# FRONT-UNIT-7.net
KiCad netlist of a schematic drawn in Altium Designer
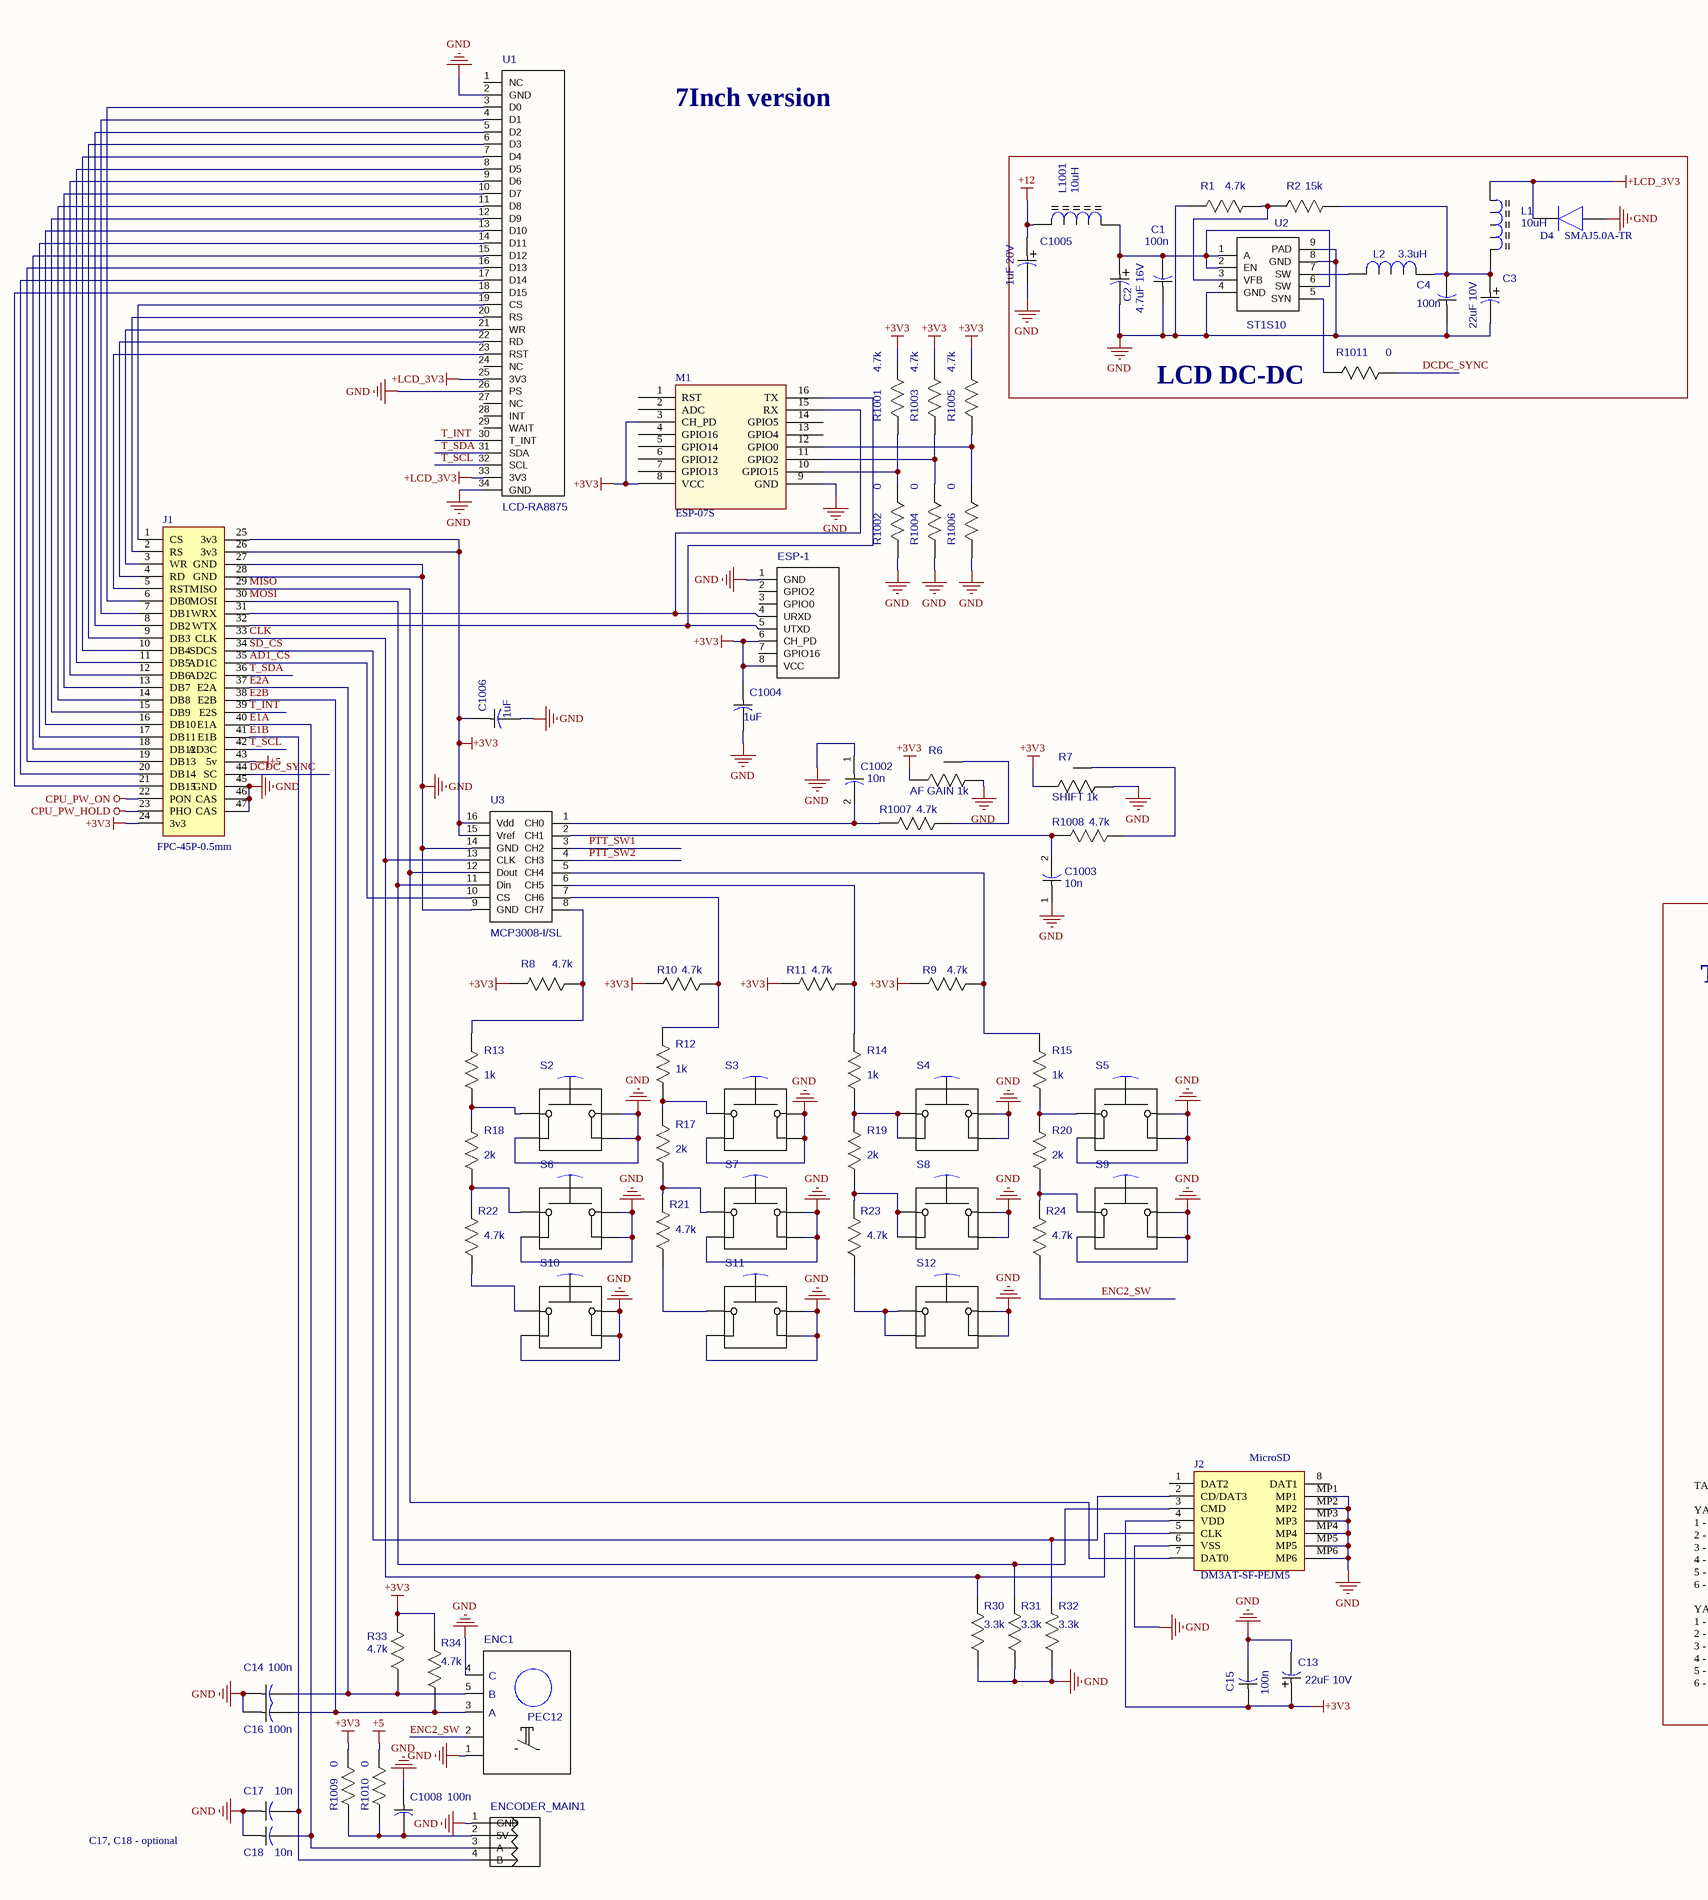
[diagram p0: FRONT-UNIT-7.SCHDOC, left]
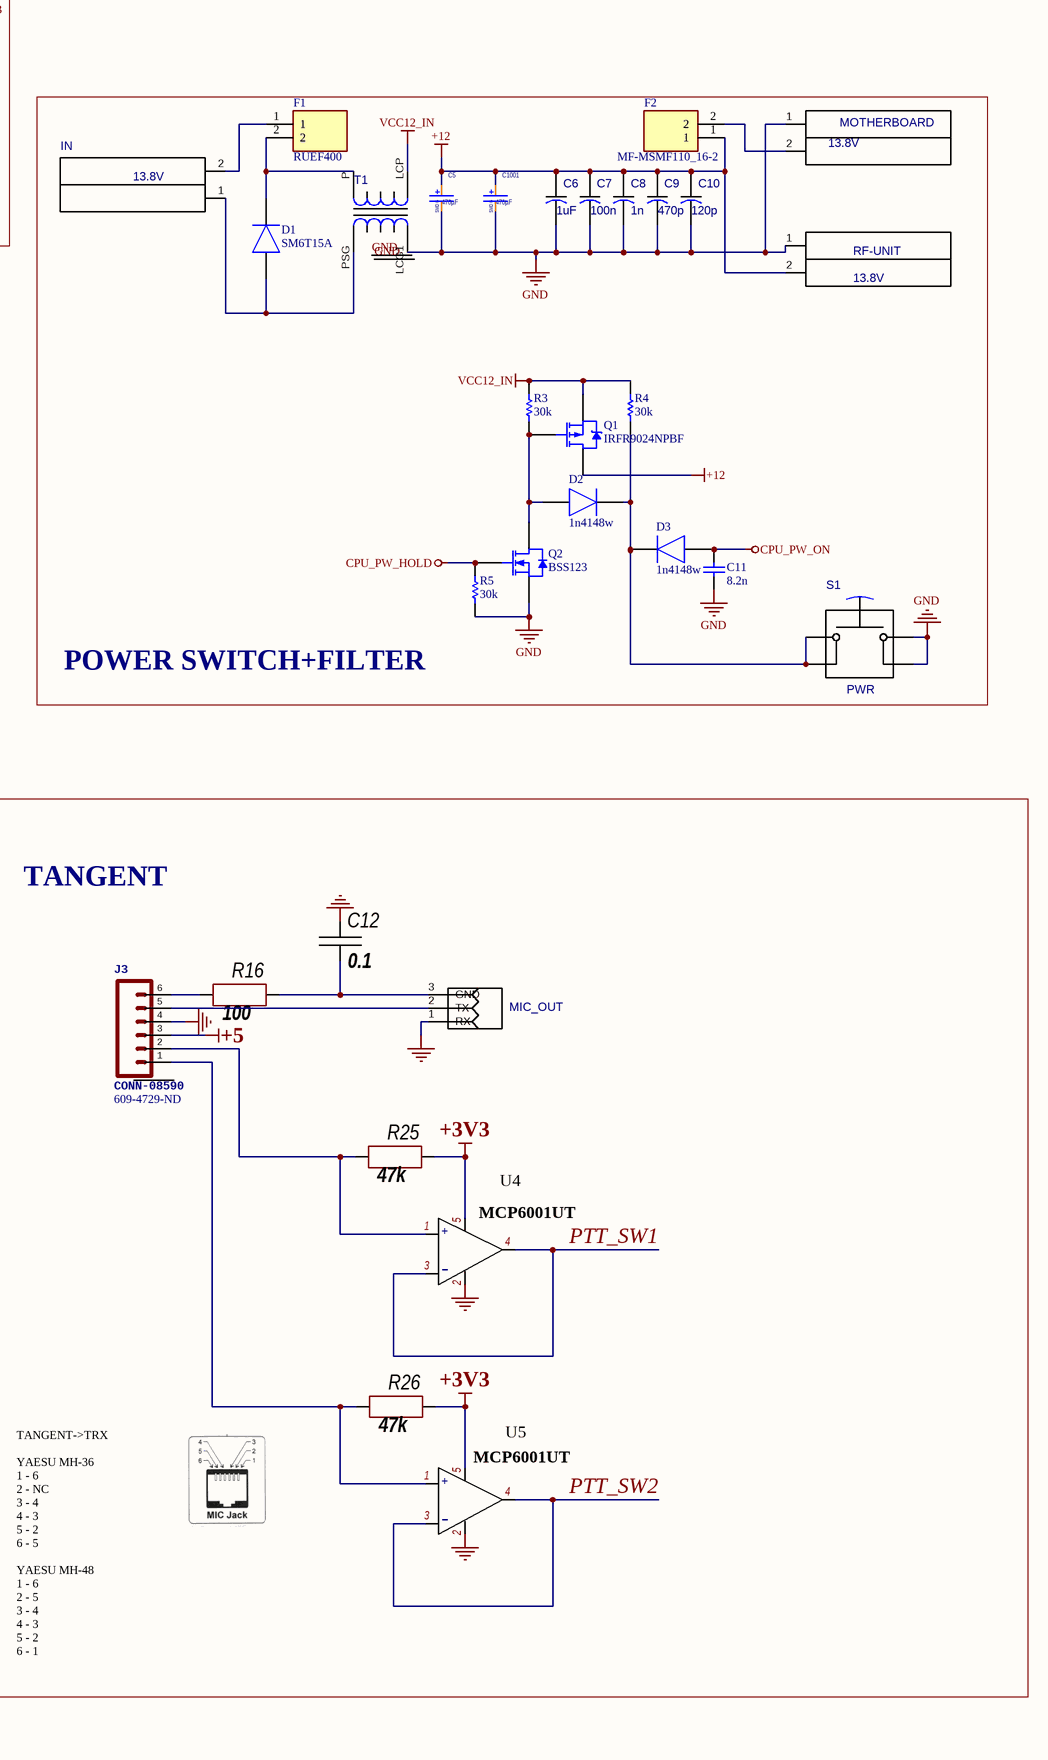
[diagram p1: FRONT-UNIT-7.SCHDOC, right]

(export (version "E")
  (design (tool "Eeschema 10.0.6"))
  (components
    (comp (ref "C1")
      (value "100n")
      (footprint "CAP_0805")
      (description "CAP_0805")
      (libsource (lib "*") (part "CAP_0805"))
    )
    (comp (ref "C2")
      (value "4.7uF 16V")
      (footprint "SMC")
      (description "CAPAE_6.6x6.6h5.4")
      (libsource (lib "*") (part "CAPAE_6.6x6.6h5.4"))
    )
    (comp (ref "C3")
      (value "22uF 10V")
      (footprint "CAPAE_4.3x4.3h5.4")
      (description "CAPAE_4.3x4.3h5.4")
      (libsource (lib "*") (part "CAPAE_4.3x4.3h5.4"))
    )
    (comp (ref "C4")
      (value "100n")
      (footprint "CAP_0805")
      (description "CAP_0805")
      (libsource (lib "FRONT-UNIT-7INCH") (part "CAP_0805"))
    )
    (comp (ref "C5")
      (value "470µF")
      (footprint "SMD-G-10X10.2")
      (description "CAP ALUM 470UF 20% 25V SMD")
      (fields
        (field (name "TOLERANCE") "±20 %")
        (field (name "VOLTAGE") "25V")
        (field (name "PUBLISHER") "Catcatcat Electronics")
      )
      (libsource (lib "CapacitorElectrolytic") (part "SMD-G 470uF 25V"))
    )
    (comp (ref "C6")
      (value "1uF")
      (footprint "CAP_1206")
      (description "CAP_1206")
      (libsource (lib "*") (part "CAP_1206"))
    )
    (comp (ref "C7")
      (value "100n")
      (footprint "CAP_1206")
      (description "CAP_1206")
      (libsource (lib "*") (part "CAP_1206"))
    )
    (comp (ref "C8")
      (value "1n")
      (footprint "CAP_1206")
      (description "CAP_1206")
      (libsource (lib "*") (part "CAP_1206"))
    )
    (comp (ref "C9")
      (value "470p")
      (footprint "CAP_1206")
      (description "CAP_1206")
      (libsource (lib "*") (part "CAP_1206"))
    )
    (comp (ref "C10")
      (value "120p")
      (footprint "CAP_1206")
      (description "CAP_1206")
      (libsource (lib "FRONT-UNIT-7INCH") (part "CAP_1206"))
    )
    (comp (ref "C11")
      (value "8.2n")
      (footprint "CAPC2013X94X50LL20T25")
      (description "CAP_1206")
      (fields
        (field (name "MANUFACTURER") "AVX Interconnect / Elco")
        (field (name "PART NUMBER") "08055C822KAT2A")
      )
      (libsource (lib "Altium Content Vault") (part "CAP"))
    )
    (comp (ref "C12")
      (value "0.1")
      (footprint "CH0805C")
      (libsource (lib "FRONT-UNIT-7INCH") (part "Capacitor"))
    )
    (comp (ref "C13")
      (value "22uF 10V")
      (footprint "EEEFC_sizeB")
      (description "EEEFC_sizeB")
      (libsource (lib "*") (part "EEEFC_sizeB"))
    )
    (comp (ref "C14")
      (value "100n")
      (footprint "CAP_0805")
      (description "CAP_0805")
      (libsource (lib "*") (part "CAP_0805"))
    )
    (comp (ref "C15")
      (value "100n")
      (footprint "CAP_0805")
      (description "CAP_0805")
      (libsource (lib "*") (part "CAP_0805"))
    )
    (comp (ref "C16")
      (value "100n")
      (footprint "CAP_0805")
      (description "CAP_0805")
      (libsource (lib "*") (part "CAP_0805"))
    )
    (comp (ref "C17")
      (value "10n")
      (footprint "CAP_0805")
      (description "CAP_0805")
      (libsource (lib "*") (part "CAP_0805"))
    )
    (comp (ref "C18")
      (value "10n")
      (footprint "CAP_0805")
      (description "CAP_0805")
      (libsource (lib "*") (part "CAP_0805"))
    )
    (comp (ref "C1001")
      (value "470µF")
      (footprint "SMD-G-10X10.2")
      (description "CAP ALUM 470UF 20% 25V SMD")
      (fields
        (field (name "TOLERANCE") "±20 %")
        (field (name "VOLTAGE") "25V")
        (field (name "PUBLISHER") "Catcatcat Electronics")
      )
      (libsource (lib "CapacitorElectrolytic") (part "SMD-G 470uF 25V"))
    )
    (comp (ref "C1002")
      (value "10n")
      (footprint "CAP_0805")
      (libsource (lib "FRONT-UNIT-7") (part "CAP_0805"))
    )
    (comp (ref "C1003")
      (value "10n")
      (footprint "CAP_0805")
      (libsource (lib "FRONT-UNIT-7") (part "CAP_0805"))
    )
    (comp (ref "C1004")
      (value "1uF")
      (footprint "CAP_1206")
      (description "CAP_1206")
      (libsource (lib "*") (part "CAP_1206"))
    )
    (comp (ref "C1005")
      (value "1uF 20V")
      (footprint "CAPAE_4.3x4.3h5.4")
      (description "CAPAE_4.3x4.3h5.4")
      (libsource (lib "*") (part "CAPAE_4.3x4.3h5.4"))
    )
    (comp (ref "C1006")
      (value "1uF")
      (footprint "CAP_1206")
      (description "CAP_1206")
      (libsource (lib "*") (part "CAP_1206"))
    )
    (comp (ref "C1008")
      (value "100n")
      (footprint "CAP_0805")
      (description "CAP_0805")
      (libsource (lib "*") (part "CAP_0805"))
    )
    (comp (ref "D1")
      (value "SM6T15A")
      (footprint "SamacSys:SMBJ36CATR")
      (description "Diode")
      (fields (field (name "MOUSER PART NUMBER") "511-SM6T15A") (field (name "RS PART NUMBER") "4864915P"))
      (libsource (lib "*") (part "SM6T15A"))
    )
    (comp (ref "D2")
      (value "1n4148w")
      (footprint "SamacSys:SOD3716X135N")
      (description "Diode")
      (libsource (lib "*") (part "1n4148w"))
    )
    (comp (ref "D3")
      (value "1n4148w")
      (footprint "SamacSys:SOD3716X135N")
      (description "Diode")
      (libsource (lib "*") (part "1n4148w"))
    )
    (comp (ref "D4")
      (value "SMAJ5.0A-TR")
      (footprint "SamacSys:SMBJ36CATR")
      (description "Diode")
      (fields
        (field (name "MANUFACTURER_PART_NUMBER") "SMLVT3V3")
        (field (name "MOUSER PART NUMBER") "511-SMLVT3V3")
      )
      (libsource (lib "*") (part "SMLVT3V3"))
    )
    (comp (ref "ENC1") (value "PEC12") (footprint "PEC12") (libsource (lib "*") (part "PEC12")))
    (comp (ref "ENCODER_MAIN1")
      (value "OPTICAL ENCODER")
      (footprint "644456-4")
      (libsource (lib "*") (part "644456-4"))
    )
    (comp (ref "ESP-1")
      (value "ESP-01 ESP8266")
      (footprint "ESP-01 ESP8266")
      (libsource (lib "*") (part "ESP-01 ESP8266"))
    )
    (comp (ref "F1")
      (value "RUEF400")
      (footprint "SamacSys:RUEF400")
      (description "Fuse")
      (fields (field (name "MOUSER PART NUMBER") "650-RUEF400") (field (name "RS PART NUMBER") "5176837P"))
      (libsource (lib "*") (part "RUEF400"))
    )
    (comp (ref "F2")
      (value "MF-MSMF110_16-2")
      (footprint "SamacSys:FUSC4632X85N")
      (description "Fuse")
      (fields
        (field (name "MANUFACTURER_PART_NUMBER") "MF-MSMF110/16-2")
        (field (name "MOUSER PART NUMBER") "652-MF-MSMF110/16-2")
      )
      (libsource (lib "*") (part "MF-MSMF110_16-2"))
    )
    (comp (ref "IN") (value "13.8V") (footprint "JX2") (description "JX2") (libsource (lib "*") (part "JX2")))
    (comp (ref "J1")
      (value "FPC-45P-0.5mm")
      (footprint "FH12S45S05SH60")
      (description "Connector")
      (fields
        (field (name "MANUFACTURER_PART_NUMBER") "FH12S-45S-0.5SH(55)")
        (field (name "MOUSER PART NUMBER") "798-FH12S-45S-05SH55")
      )
      (libsource (lib "*") (part "FH12S-45S-0.5SH_55_"))
    )
    (comp (ref "J2")
      (value "DM3AT-SF-PEJM5")
      (footprint "SamacSys:DM3ATSFPEJM5")
      (description "Connector")
      (libsource (lib "*") (part "DM3AT-SF-PEJM5"))
    )
    (comp (ref "J3")
      (value "CONN-08590")
      (footprint "RJ11-6")
      (description "RJ11 6P6C")
      (fields (field (name "SUPPLIER PART NUMBER 1") "609-4729-ND"))
      (libsource (lib "AltiumLibraryDDT") (part "RJ11-6"))
    )
    (comp (ref "L1")
      (value "10uH")
      (footprint "IND_7x7")
      (description "Inductor")
      (libsource (lib "FRONT-UNIT-7INCH") (part "IND_FERRITE_CORE"))
    )
    (comp (ref "L2")
      (value "3.3uH")
      (footprint "IND_1812")
      (description "IND_1812")
      (libsource (lib "*") (part "IND_1812"))
    )
    (comp (ref "L1001")
      (value "10uH")
      (footprint "IND_7x7")
      (description "Inductor")
      (libsource (lib "FRONT-UNIT-7INCH") (part "IND_FERRITE_CORE"))
    )
    (comp (ref "M1")
      (value "ESP-07S")
      (footprint "modules:ESP-07S")
      (libsource (lib "modules") (part "ESP-07S"))
    )
    (comp (ref "MIC_OUT")
      (value "51022-0300")
      (footprint "51022-0200 - duplicate")
      (libsource (lib "MOTHERBOARD") (part "51022-0300"))
    )
    (comp (ref "MOTHERBOARD")
      (value "13.8V")
      (footprint "JX2")
      (description "JX2")
      (libsource (lib "*") (part "JX2"))
    )
    (comp (ref "Q1")
      (value "IRFR9024NPBF")
      (footprint "ONSC-DPAK-3-369C-01_V")
      (description "IRFR9024NPBF, Транзистор, Р-канал 55В 11А")
      (fields (field (name "MANUFACTURER") "On Semiconductor") (field (name "PARTNUMBER") "NTD2955G"))
      (libsource (lib "Altium Content Vault") (part "ONSC-PMOS-G1S3D4-3_B"))
    )
    (comp (ref "Q2")
      (value "BSS123")
      (footprint "FAIR-SOT23-3_V")
      (fields (field (name "MANUFACTURER") "Fairchild"))
      (libsource (lib "Altium Content Vault") (part "NEMOS-GSD-3"))
    )
    (comp (ref "R1")
      (value "4.7k")
      (footprint "RES_0805")
      (description "RES_0805")
      (libsource (lib "") (part "RES_0805_1"))
    )
    (comp (ref "R2")
      (value "15k")
      (footprint "RES_0805")
      (description "RES_0805")
      (libsource (lib "") (part "RES_0805_1"))
    )
    (comp (ref "R3")
      (value "30k")
      (footprint "RESC2013X60X40NL20T25")
      (description "RES_0805")
      (fields (field (name "MANUFACTURER") "Panasonic") (field (name "PART NUMBER") "ERA-6AEB303V"))
      (libsource (lib "Altium Content Vault") (part "RES"))
    )
    (comp (ref "R4")
      (value "30k")
      (footprint "RESC2013X60X40NL20T25")
      (description "RES_0805")
      (fields (field (name "MANUFACTURER") "Panasonic") (field (name "PART NUMBER") "ERA-6AEB303V"))
      (libsource (lib "Altium Content Vault") (part "RES"))
    )
    (comp (ref "R5")
      (value "30k")
      (footprint "RESC2013X60X40NL20T25")
      (description "RES_0805")
      (fields (field (name "MANUFACTURER") "Panasonic") (field (name "PART NUMBER") "ERA-6AEB303V"))
      (libsource (lib "Altium Content Vault") (part "RES"))
    )
    (comp (ref "R6")
      (value "AF GAIN 1k")
      (footprint "PTV09")
      (description "Adjustable Resistor PTV09")
      (fields (field (name "Comment") "ptv09a-4225f-b102"))
      (libsource (lib "*") (part "PTV09"))
    )
    (comp (ref "R7")
      (value "SHIFT 1k")
      (footprint "PTV09")
      (description "Adjustable Resistor PTV09")
      (fields (field (name "Comment") "ptv09a-4225f-b102"))
      (libsource (lib "*") (part "PTV09"))
    )
    (comp (ref "R8")
      (value "4.7k")
      (footprint "RES_0805")
      (description "RES_0805")
      (libsource (lib "*") (part "RES_0805"))
    )
    (comp (ref "R9")
      (value "4.7k")
      (footprint "RES_0805")
      (description "RES_0805")
      (libsource (lib "*") (part "RES_0805"))
    )
    (comp (ref "R10")
      (value "4.7k")
      (footprint "RES_0805")
      (description "RES_0805")
      (libsource (lib "*") (part "RES_0805"))
    )
    (comp (ref "R11")
      (value "4.7k")
      (footprint "RES_0805")
      (description "RES_0805")
      (libsource (lib "*") (part "RES_0805"))
    )
    (comp (ref "R12")
      (value "1k")
      (footprint "RES_0805")
      (description "RES_0805")
      (libsource (lib "*") (part "RES_0805"))
    )
    (comp (ref "R13")
      (value "1k")
      (footprint "RES_0805")
      (description "RES_0805")
      (libsource (lib "*") (part "RES_0805"))
    )
    (comp (ref "R14")
      (value "1k")
      (footprint "RES_0805")
      (description "RES_0805")
      (libsource (lib "*") (part "RES_0805"))
    )
    (comp (ref "R15")
      (value "1k")
      (footprint "RES_0805")
      (description "RES_0805")
      (libsource (lib "*") (part "RES_0805"))
    )
    (comp (ref "R16")
      (value "100")
      (footprint "FRONT-UNIT-7INCH:CH0805R")
      (libsource (lib "Discrete") (part "Resistor"))
    )
    (comp (ref "R17")
      (value "2k")
      (footprint "RES_0805")
      (description "RES_0805")
      (libsource (lib "*") (part "RES_0805"))
    )
    (comp (ref "R18")
      (value "2k")
      (footprint "RES_0805")
      (description "RES_0805")
      (libsource (lib "*") (part "RES_0805"))
    )
    (comp (ref "R19")
      (value "2k")
      (footprint "RES_0805")
      (description "RES_0805")
      (libsource (lib "*") (part "RES_0805"))
    )
    (comp (ref "R20")
      (value "2k")
      (footprint "RES_0805")
      (description "RES_0805")
      (libsource (lib "*") (part "RES_0805"))
    )
    (comp (ref "R21")
      (value "4.7k")
      (footprint "RES_0805")
      (description "RES_0805")
      (libsource (lib "*") (part "RES_0805"))
    )
    (comp (ref "R22")
      (value "4.7k")
      (footprint "RES_0805")
      (description "RES_0805")
      (libsource (lib "*") (part "RES_0805"))
    )
    (comp (ref "R23")
      (value "4.7k")
      (footprint "RES_0805")
      (description "RES_0805")
      (libsource (lib "*") (part "RES_0805"))
    )
    (comp (ref "R24")
      (value "4.7k")
      (footprint "RES_0805")
      (description "RES_0805")
      (libsource (lib "*") (part "RES_0805"))
    )
    (comp (ref "R25")
      (value "47k")
      (footprint "FRONT-UNIT-7INCH:CH0805R")
      (libsource (lib "Discrete") (part "Resistor"))
    )
    (comp (ref "R26")
      (value "47k")
      (footprint "FRONT-UNIT-7INCH:CH0805C")
      (libsource (lib "Discrete") (part "Resistor"))
    )
    (comp (ref "R30")
      (value "3.3k")
      (footprint "RES_0805")
      (description "RES_0805")
      (libsource (lib "*") (part "RES_0805"))
    )
    (comp (ref "R31")
      (value "3.3k")
      (footprint "RES_0805")
      (description "RES_0805")
      (libsource (lib "*") (part "RES_0805"))
    )
    (comp (ref "R32")
      (value "3.3k")
      (footprint "RES_0805")
      (description "RES_0805")
      (libsource (lib "*") (part "RES_0805"))
    )
    (comp (ref "R33")
      (value "4.7k")
      (footprint "RES_0805")
      (description "RES_0805")
      (libsource (lib "*") (part "RES_0805"))
    )
    (comp (ref "R34")
      (value "4.7k")
      (footprint "RES_0805")
      (description "RES_0805")
      (libsource (lib "*") (part "RES_0805"))
    )
    (comp (ref "R1001")
      (value "4.7k")
      (footprint "RES_0805")
      (description "RES_0805")
      (libsource (lib "*") (part "RES_0805"))
    )
    (comp (ref "R1002")
      (value "0")
      (footprint "RES_0805")
      (description "RES_0805")
      (libsource (lib "*") (part "RES_0805"))
    )
    (comp (ref "R1003")
      (value "4.7k")
      (footprint "RES_0805")
      (description "RES_0805")
      (libsource (lib "*") (part "RES_0805"))
    )
    (comp (ref "R1004")
      (value "0")
      (footprint "RES_0805")
      (description "RES_0805")
      (libsource (lib "*") (part "RES_0805"))
    )
    (comp (ref "R1005")
      (value "4.7k")
      (footprint "RES_0805")
      (description "RES_0805")
      (libsource (lib "*") (part "RES_0805"))
    )
    (comp (ref "R1006")
      (value "0")
      (footprint "RES_0805")
      (description "RES_0805")
      (libsource (lib "*") (part "RES_0805"))
    )
    (comp (ref "R1007")
      (value "4.7k")
      (footprint "RES_0805")
      (description "RES_0805")
      (libsource (lib "*") (part "RES_0805"))
    )
    (comp (ref "R1008")
      (value "4.7k")
      (footprint "RES_0805")
      (description "RES_0805")
      (libsource (lib "*") (part "RES_0805"))
    )
    (comp (ref "R1009")
      (value "0")
      (footprint "RES_0805")
      (description "RES_0805")
      (libsource (lib "*") (part "RES_0805"))
    )
    (comp (ref "R1010")
      (value "0")
      (footprint "RES_0805")
      (description "RES_0805")
      (libsource (lib "*") (part "RES_0805"))
    )
    (comp (ref "R1011")
      (value "0")
      (footprint "RES_0805")
      (description "RES_0805")
      (libsource (lib "") (part "RES_0805_1"))
    )
    (comp (ref "RF-UNIT")
      (value "13.8V")
      (footprint "JX2")
      (description "JX2")
      (libsource (lib "*") (part "JX2"))
    )
    (comp (ref "S1")
      (value "PWR")
      (footprint "PTS645SK50LFS")
      (description "PTS645SK50LFS")
      (libsource (lib "*") (part "PTS645SK50LFS"))
    )
    (comp (ref "S2")
      (value "PTS645SK50LFS")
      (footprint "L-X")
      (fields (field (name "LCSC PART #") "test"))
      (libsource (lib "*") (part "PTS645SK50LFS"))
    )
    (comp (ref "S3") (value "PTS645SK50LFS") (footprint "L-X") (libsource (lib "*") (part "PTS645SK50LFS")))
    (comp (ref "S4")
      (value "PTS645SK50LFS")
      (footprint "PTS645SK50LFS")
      (libsource (lib "*") (part "PTS645SK50LFS"))
    )
    (comp (ref "S5") (value "PTS645SK50LFS") (footprint "L-X") (libsource (lib "*") (part "PTS645SK50LFS")))
    (comp (ref "S6") (value "PTS645SK50LFS") (footprint "L-X") (libsource (lib "*") (part "PTS645SK50LFS")))
    (comp (ref "S7") (value "PTS645SK50LFS") (footprint "L-X") (libsource (lib "*") (part "PTS645SK50LFS")))
    (comp (ref "S8")
      (value "PTS645SK50LFS")
      (footprint "PTS645SK50LFS")
      (libsource (lib "*") (part "PTS645SK50LFS"))
    )
    (comp (ref "S9") (value "PTS645SK50LFS") (footprint "L-X") (libsource (lib "*") (part "PTS645SK50LFS")))
    (comp (ref "S10") (value "PTS645SK50LFS") (footprint "L-X") (libsource (lib "*") (part "PTS645SK50LFS")))
    (comp (ref "S11") (value "PTS645SK50LFS") (footprint "L-X") (libsource (lib "*") (part "PTS645SK50LFS")))
    (comp (ref "S12")
      (value "PTS645SK50LFS")
      (footprint "PTS645SK50LFS")
      (libsource (lib "*") (part "PTS645SK50LFS"))
    )
    (comp (ref "T1")
      (value "TRANSF_ICORE")
      (footprint "TRANSF_ICORE")
      (libsource (lib "FRONT-UNIT-7") (part "TRANSF_ICORE"))
    )
    (comp (ref "U1")
      (value "LCD-RA8875")
      (footprint "LCD-RA8875")
      (libsource (lib "FRONT-UNIT-7INCH") (part "LCD-RA8875"))
    )
    (comp (ref "U2") (value "ST1S10") (footprint "ST1S10") (libsource (lib "*") (part "ST1S10")))
    (comp (ref "U3")
      (value "MCP3008-I/SL")
      (footprint "MCP3008-I/SL")
      (libsource (lib "*") (part "MCP3008-I/SL"))
    )
    (comp (ref "U4")
      (value "MCP6001UT")
      (footprint "SOT23-5")
      (libsource (lib "Analog") (part "MCP6001UT_1"))
    )
    (comp (ref "U5")
      (value "MCP6001UT")
      (footprint "SOT23-5")
      (libsource (lib "Analog") (part "MCP6001UT_1"))
    )
  )
  (nets
    (net (code "1") (name "+3V3") (class "Default")
      (node (ref "C1004") (pin "1") (pinfunction "1_1") (pintype "passive"))
      (node (ref "C1006") (pin "1") (pinfunction "1_1") (pintype "passive"))
      (node (ref "C13") (pin "1") (pinfunction "PLUS_1") (pintype "passive"))
      (node (ref "C15") (pin "1") (pinfunction "1_1") (pintype "passive"))
      (node (ref "ESP-1") (pin "6") (pinfunction "CH_PD_6") (pintype "passive"))
      (node (ref "ESP-1") (pin "8") (pinfunction "VCC_8") (pintype "passive"))
      (node (ref "J1") (pin "24") (pinfunction "3v3_24") (pintype "passive"))
      (node (ref "J1") (pin "25") (pinfunction "3v3_25") (pintype "passive"))
      (node (ref "J1") (pin "26") (pinfunction "3v3_26") (pintype "passive"))
      (node (ref "J2") (pin "4") (pinfunction "VDD_4") (pintype "passive"))
      (node (ref "M1") (pin "3") (pinfunction "CH_PD_3") (pintype "passive"))
      (node (ref "M1") (pin "8") (pinfunction "VCC_8") (pintype "passive"))
      (node (ref "R10") (pin "2") (pinfunction "2_2") (pintype "passive"))
      (node (ref "R1001") (pin "1") (pinfunction "1_1") (pintype "passive"))
      (node (ref "R1003") (pin "1") (pinfunction "1_1") (pintype "passive"))
      (node (ref "R1005") (pin "1") (pinfunction "1_1") (pintype "passive"))
      (node (ref "R1009") (pin "2") (pinfunction "2_2") (pintype "passive"))
      (node (ref "R11") (pin "2") (pinfunction "2_2") (pintype "passive"))
      (node (ref "R25") (pin "2") (pinfunction "2_2") (pintype "passive"))
      (node (ref "R26") (pin "2") (pinfunction "2_2") (pintype "passive"))
      (node (ref "R33") (pin "2") (pinfunction "2_2") (pintype "passive"))
      (node (ref "R34") (pin "2") (pinfunction "2_2") (pintype "passive"))
      (node (ref "R6") (pin "1") (pinfunction "CW_1") (pintype "passive"))
      (node (ref "R7") (pin "1") (pinfunction "CW_1") (pintype "passive"))
      (node (ref "R8") (pin "2") (pinfunction "2_2") (pintype "passive"))
      (node (ref "R9") (pin "2") (pinfunction "2_2") (pintype "passive"))
      (node (ref "U3") (pin "15") (pinfunction "Vref_15") (pintype "passive"))
      (node (ref "U3") (pin "16") (pinfunction "Vdd_16") (pintype "passive"))
      (node (ref "U4") (pin "5") (pinfunction "5_5") (pintype "passive"))
      (node (ref "U5") (pin "5") (pinfunction "5_5") (pintype "passive"))
    )
    (net (code "2") (name "+5") (class "Default")
      (node (ref "J1") (pin "43") (pinfunction "5v_43") (pintype "passive"))
      (node (ref "J3") (pin "3") (pinfunction "3_3") (pintype "passive"))
      (node (ref "R1010") (pin "2") (pinfunction "2_2") (pintype "passive"))
    )
    (net (code "3") (name "+12") (class "Default")
      (node (ref "C10") (pin "1") (pinfunction "1_1") (pintype "passive"))
      (node (ref "C1001") (pin "1") (pinfunction "1_1") (pintype "passive"))
      (node (ref "C1005") (pin "1") (pinfunction "PLUS_1") (pintype "passive"))
      (node (ref "C5") (pin "1") (pinfunction "1_1") (pintype "passive"))
      (node (ref "C6") (pin "1") (pinfunction "1_1") (pintype "passive"))
      (node (ref "C7") (pin "1") (pinfunction "1_1") (pintype "passive"))
      (node (ref "C8") (pin "1") (pinfunction "1_1") (pintype "passive"))
      (node (ref "C9") (pin "1") (pinfunction "1_1") (pintype "passive"))
      (node (ref "F2") (pin "1") (pinfunction "1_1") (pintype "passive"))
      (node (ref "L1001") (pin "1") (pinfunction "A_1") (pintype "passive"))
      (node (ref "Q1") (pin "4") (pinfunction "D_4") (pintype "passive"))
      (node (ref "RF-UNIT") (pin "2") (pinfunction "1_2") (pintype "passive"))
    )
    (net (code "4") (name "+LCD_3V3") (class "Default")
      (node (ref "D4") (pin "1") (pinfunction "K_1") (pintype "passive"))
      (node (ref "L1") (pin "1") (pinfunction "A_1") (pintype "passive"))
      (node (ref "U1") (pin "25") (pinfunction "3V3_25") (pintype "passive"))
      (node (ref "U1") (pin "33") (pinfunction "3V3_33") (pintype "passive"))
    )
    (net (code "5") (name "/AD1_CS") (class "Default")
      (node (ref "J1") (pin "35") (pinfunction "AD1C_35") (pintype "passive"))
      (node (ref "U3") (pin "10") (pinfunction "CS_10") (pintype "passive"))
    )
    (net (code "6") (name "/CLK") (class "Default")
      (node (ref "J1") (pin "33") (pinfunction "CLK_33") (pintype "passive"))
      (node (ref "J2") (pin "5") (pinfunction "CLK_5") (pintype "passive"))
      (node (ref "R30") (pin "2") (pinfunction "2_2") (pintype "passive"))
      (node (ref "U3") (pin "13") (pinfunction "CLK_13") (pintype "passive"))
    )
    (net (code "7") (name "/DCDC_SYNC") (class "Default")
      (node (ref "J1") (pin "44") (pinfunction "SC_44") (pintype "passive"))
      (node (ref "R1011") (pin "2") (pinfunction "2_2") (pintype "passive"))
    )
    (net (code "8") (name "/E1A") (class "Default")
      (node (ref "C18") (pin "2") (pinfunction "2_2") (pintype "passive"))
      (node (ref "ENCODER_MAIN1") (pin "3") (pinfunction "A_3") (pintype "passive"))
      (node (ref "J1") (pin "40") (pinfunction "E1A_40") (pintype "passive"))
    )
    (net (code "9") (name "/E1B") (class "Default")
      (node (ref "C17") (pin "2") (pinfunction "2_2") (pintype "passive"))
      (node (ref "ENCODER_MAIN1") (pin "4") (pinfunction "B_4") (pintype "passive"))
      (node (ref "J1") (pin "41") (pinfunction "E1B_41") (pintype "passive"))
    )
    (net (code "10") (name "/E2A") (class "Default")
      (node (ref "C14") (pin "2") (pinfunction "2_2") (pintype "passive"))
      (node (ref "ENC1") (pin "5") (pinfunction "B_5") (pintype "passive"))
      (node (ref "J1") (pin "37") (pinfunction "E2A_37") (pintype "passive"))
      (node (ref "R33") (pin "1") (pinfunction "1_1") (pintype "passive"))
    )
    (net (code "11") (name "/E2B") (class "Default")
      (node (ref "C16") (pin "2") (pinfunction "2_2") (pintype "passive"))
      (node (ref "ENC1") (pin "3") (pinfunction "A_3") (pintype "passive"))
      (node (ref "J1") (pin "38") (pinfunction "E2B_38") (pintype "passive"))
      (node (ref "R34") (pin "1") (pinfunction "1_1") (pintype "passive"))
    )
    (net (code "12") (name "/ENC2_SW") (class "Default")
      (node (ref "ENC1") (pin "2") (pinfunction "2_2") (pintype "passive"))
      (node (ref "R24") (pin "1") (pinfunction "1_1") (pintype "passive"))
    )
    (net (code "13") (name "/MISO") (class "Default")
      (node (ref "J1") (pin "29") (pinfunction "MISO_29") (pintype "passive"))
      (node (ref "J2") (pin "7") (pinfunction "DAT0_7") (pintype "passive"))
      (node (ref "U3") (pin "12") (pinfunction "Dout_12") (pintype "passive"))
    )
    (net (code "14") (name "/MOSI") (class "Default")
      (node (ref "J1") (pin "30") (pinfunction "MOSI_30") (pintype "passive"))
      (node (ref "J2") (pin "3") (pinfunction "CMD_3") (pintype "passive"))
      (node (ref "R31") (pin "2") (pinfunction "2_2") (pintype "passive"))
      (node (ref "U3") (pin "11") (pinfunction "Din_11") (pintype "passive"))
    )
    (net (code "15") (name "/PTT_SW1") (class "Default")
      (node (ref "U3") (pin "3") (pinfunction "CH2_3") (pintype "passive"))
      (node (ref "U4") (pin "3") (pinfunction "3_3") (pintype "passive"))
      (node (ref "U4") (pin "4") (pinfunction "4_4") (pintype "passive"))
    )
    (net (code "16") (name "/PTT_SW2") (class "Default")
      (node (ref "U3") (pin "4") (pinfunction "CH3_4") (pintype "passive"))
      (node (ref "U5") (pin "3") (pinfunction "3_3") (pintype "passive"))
      (node (ref "U5") (pin "4") (pinfunction "4_4") (pintype "passive"))
    )
    (net (code "17") (name "/SD_CS") (class "Default")
      (node (ref "J1") (pin "34") (pinfunction "SDCS_34") (pintype "passive"))
      (node (ref "J2") (pin "2") (pinfunction "CD/DAT3_2") (pintype "passive"))
      (node (ref "R32") (pin "2") (pinfunction "2_2") (pintype "passive"))
    )
    (net (code "18") (name "/T_INT") (class "Default")
      (node (ref "J1") (pin "39") (pinfunction "E2S_39") (pintype "passive"))
      (node (ref "U1") (pin "30") (pinfunction "T_INT_30") (pintype "passive"))
    )
    (net (code "19") (name "/T_SCL") (class "Default")
      (node (ref "J1") (pin "42") (pinfunction "AD3C_42") (pintype "passive"))
      (node (ref "U1") (pin "32") (pinfunction "SCL_32") (pintype "passive"))
    )
    (net (code "20") (name "/T_SDA") (class "Default")
      (node (ref "J1") (pin "36") (pinfunction "AD2C_36") (pintype "passive"))
      (node (ref "U1") (pin "31") (pinfunction "SDA_31") (pintype "passive"))
    )
    (net (code "21") (name "CPU_PW_HOLD") (class "Default")
      (node (ref "J1") (pin "23") (pinfunction "PHO_23") (pintype "passive"))
      (node (ref "Q2") (pin "1") (pinfunction "G_1") (pintype "passive"))
      (node (ref "R5") (pin "2") (pinfunction "2_2") (pintype "passive"))
    )
    (net (code "22") (name "CPU_PW_ON") (class "Default")
      (node (ref "C11") (pin "2") (pinfunction "2_2") (pintype "passive"))
      (node (ref "D3") (pin "2") (pinfunction "A_2") (pintype "passive"))
      (node (ref "J1") (pin "22") (pinfunction "PON_22") (pintype "passive"))
    )
    (net (code "23") (name "GND") (class "Default")
      (node (ref "C1") (pin "1") (pinfunction "1_1") (pintype "passive"))
      (node (ref "C10") (pin "2") (pinfunction "2_2") (pintype "passive"))
      (node (ref "C1001") (pin "2") (pinfunction "2_2") (pintype "passive"))
      (node (ref "C1002") (pin "1") (pinfunction "1_1") (pintype "passive"))
      (node (ref "C1003") (pin "1") (pinfunction "1_1") (pintype "passive"))
      (node (ref "C1004") (pin "2") (pinfunction "2_2") (pintype "passive"))
      (node (ref "C1005") (pin "2") (pinfunction "MINUS_2") (pintype "passive"))
      (node (ref "C1006") (pin "2") (pinfunction "2_2") (pintype "passive"))
      (node (ref "C1008") (pin "1") (pinfunction "1_1") (pintype "passive"))
      (node (ref "C11") (pin "1") (pinfunction "1_1") (pintype "passive"))
      (node (ref "C12") (pin "1") (pinfunction "1_1") (pintype "power_in"))
      (node (ref "C13") (pin "2") (pinfunction "MINUS_2") (pintype "passive"))
      (node (ref "C14") (pin "1") (pinfunction "1_1") (pintype "passive"))
      (node (ref "C15") (pin "2") (pinfunction "2_2") (pintype "passive"))
      (node (ref "C16") (pin "1") (pinfunction "1_1") (pintype "passive"))
      (node (ref "C17") (pin "1") (pinfunction "1_1") (pintype "passive"))
      (node (ref "C18") (pin "1") (pinfunction "1_1") (pintype "passive"))
      (node (ref "C2") (pin "2") (pinfunction "MINUS_2") (pintype "passive"))
      (node (ref "C3") (pin "2") (pinfunction "MINUS_2") (pintype "passive"))
      (node (ref "C4") (pin "1") (pinfunction "1_1") (pintype "passive"))
      (node (ref "C5") (pin "2") (pinfunction "2_2") (pintype "passive"))
      (node (ref "C6") (pin "2") (pinfunction "2_2") (pintype "passive"))
      (node (ref "C7") (pin "2") (pinfunction "2_2") (pintype "passive"))
      (node (ref "C8") (pin "2") (pinfunction "2_2") (pintype "passive"))
      (node (ref "C9") (pin "2") (pinfunction "2_2") (pintype "passive"))
      (node (ref "D4") (pin "2") (pinfunction "A_2") (pintype "passive"))
      (node (ref "ENC1") (pin "1") (pinfunction "1_1") (pintype "passive"))
      (node (ref "ENC1") (pin "4") (pinfunction "C_4") (pintype "passive"))
      (node (ref "ENCODER_MAIN1") (pin "1") (pinfunction "GND_1") (pintype "passive"))
      (node (ref "ESP-1") (pin "1") (pinfunction "GND_1") (pintype "passive"))
      (node (ref "J1") (pin "27") (pinfunction "GND_27") (pintype "passive"))
      (node (ref "J1") (pin "28") (pinfunction "GND_28") (pintype "passive"))
      (node (ref "J1") (pin "45") (pinfunction "GND_45") (pintype "passive"))
      (node (ref "J1") (pin "46") (pinfunction "CAS_46") (pintype "passive"))
      (node (ref "J1") (pin "47") (pinfunction "CAS_47") (pintype "passive"))
      (node (ref "J2") (pin "6") (pinfunction "VSS_6") (pintype "passive"))
      (node (ref "J2") (pin "MP1") (pinfunction "MP1_MP1") (pintype "passive"))
      (node (ref "J2") (pin "MP2") (pinfunction "MP2_MP2") (pintype "passive"))
      (node (ref "J2") (pin "MP3") (pinfunction "MP3_MP3") (pintype "passive"))
      (node (ref "J2") (pin "MP4") (pinfunction "MP4_MP4") (pintype "passive"))
      (node (ref "J2") (pin "MP5") (pinfunction "MP5_MP5") (pintype "passive"))
      (node (ref "J2") (pin "MP6") (pinfunction "MP6_MP6") (pintype "passive"))
      (node (ref "J3") (pin "4") (pinfunction "4_4") (pintype "passive"))
      (node (ref "M1") (pin "9") (pinfunction "GND_9") (pintype "passive"))
      (node (ref "MIC_OUT") (pin "1") (pinfunction "RX_1") (pintype "passive"))
      (node (ref "MOTHERBOARD") (pin "1") (pinfunction "2_1") (pintype "passive"))
      (node (ref "Q2") (pin "2") (pinfunction "S_2") (pintype "passive"))
      (node (ref "R1") (pin "1") (pinfunction "1_1") (pintype "passive"))
      (node (ref "R1002") (pin "2") (pinfunction "2_2") (pintype "passive"))
      (node (ref "R1004") (pin "2") (pinfunction "2_2") (pintype "passive"))
      (node (ref "R1006") (pin "2") (pinfunction "2_2") (pintype "passive"))
      (node (ref "R30") (pin "1") (pinfunction "1_1") (pintype "passive"))
      (node (ref "R31") (pin "1") (pinfunction "1_1") (pintype "passive"))
      (node (ref "R32") (pin "1") (pinfunction "1_1") (pintype "passive"))
      (node (ref "R5") (pin "1") (pinfunction "1_1") (pintype "passive"))
      (node (ref "R6") (pin "3") (pinfunction "CCW_3") (pintype "passive"))
      (node (ref "R7") (pin "3") (pinfunction "CCW_3") (pintype "passive"))
      (node (ref "RF-UNIT") (pin "1") (pinfunction "2_1") (pintype "passive"))
      (node (ref "S1") (pin "3") (pinfunction "B_3") (pintype "passive"))
      (node (ref "S1") (pin "4") (pinfunction "B_4") (pintype "passive"))
      (node (ref "S10") (pin "2") (pinfunction "A_2") (pintype "passive"))
      (node (ref "S10") (pin "3") (pinfunction "B_3") (pintype "passive"))
      (node (ref "S10") (pin "4") (pinfunction "B_4") (pintype "passive"))
      (node (ref "S11") (pin "2") (pinfunction "A_2") (pintype "passive"))
      (node (ref "S11") (pin "3") (pinfunction "B_3") (pintype "passive"))
      (node (ref "S11") (pin "4") (pinfunction "B_4") (pintype "passive"))
      (node (ref "S12") (pin "3") (pinfunction "B_3") (pintype "passive"))
      (node (ref "S12") (pin "4") (pinfunction "B_4") (pintype "passive"))
      (node (ref "S2") (pin "2") (pinfunction "A_2") (pintype "passive"))
      (node (ref "S2") (pin "3") (pinfunction "B_3") (pintype "passive"))
      (node (ref "S2") (pin "4") (pinfunction "B_4") (pintype "passive"))
      (node (ref "S3") (pin "2") (pinfunction "A_2") (pintype "passive"))
      (node (ref "S3") (pin "3") (pinfunction "B_3") (pintype "passive"))
      (node (ref "S3") (pin "4") (pinfunction "B_4") (pintype "passive"))
      (node (ref "S4") (pin "3") (pinfunction "B_3") (pintype "passive"))
      (node (ref "S4") (pin "4") (pinfunction "B_4") (pintype "passive"))
      (node (ref "S5") (pin "2") (pinfunction "A_2") (pintype "passive"))
      (node (ref "S5") (pin "3") (pinfunction "B_3") (pintype "passive"))
      (node (ref "S5") (pin "4") (pinfunction "B_4") (pintype "passive"))
      (node (ref "S6") (pin "2") (pinfunction "A_2") (pintype "passive"))
      (node (ref "S6") (pin "3") (pinfunction "B_3") (pintype "passive"))
      (node (ref "S6") (pin "4") (pinfunction "B_4") (pintype "passive"))
      (node (ref "S7") (pin "2") (pinfunction "A_2") (pintype "passive"))
      (node (ref "S7") (pin "3") (pinfunction "B_3") (pintype "passive"))
      (node (ref "S7") (pin "4") (pinfunction "B_4") (pintype "passive"))
      (node (ref "S8") (pin "3") (pinfunction "B_3") (pintype "passive"))
      (node (ref "S8") (pin "4") (pinfunction "B_4") (pintype "passive"))
      (node (ref "S9") (pin "2") (pinfunction "A_2") (pintype "passive"))
      (node (ref "S9") (pin "3") (pinfunction "B_3") (pintype "passive"))
      (node (ref "S9") (pin "4") (pinfunction "B_4") (pintype "passive"))
      (node (ref "T1") (pin "LCG1") (pinfunction "S2_LCG1") (pintype "passive"))
      (node (ref "T1") (pin "LCG2") (pinfunction "LCG2_LCG2") (pintype "passive"))
      (node (ref "T1") (pin "LCG3") (pinfunction "LCG3_LCG3") (pintype "passive"))
      (node (ref "U1") (pin "2") (pinfunction "GND_2") (pintype "passive"))
      (node (ref "U1") (pin "26") (pinfunction "PS_26") (pintype "passive"))
      (node (ref "U1") (pin "34") (pinfunction "GND_34") (pintype "passive"))
      (node (ref "U2") (pin "4") (pinfunction "GND_4") (pintype "passive"))
      (node (ref "U2") (pin "8") (pinfunction "GND_8") (pintype "passive"))
      (node (ref "U2") (pin "9") (pinfunction "PAD_9") (pintype "passive"))
      (node (ref "U3") (pin "14") (pinfunction "GND_14") (pintype "passive"))
      (node (ref "U3") (pin "9") (pinfunction "GND_9") (pintype "passive"))
      (node (ref "U4") (pin "2") (pinfunction "2_2") (pintype "passive"))
      (node (ref "U5") (pin "2") (pinfunction "2_2") (pintype "passive"))
    )
    (net (code "24") (name "Net-(C2-PLUS)") (class "Default")
      (node (ref "C1") (pin "2") (pinfunction "2_2") (pintype "passive"))
      (node (ref "C2") (pin "1") (pinfunction "PLUS_1") (pintype "passive"))
      (node (ref "L1001") (pin "2") (pinfunction "B_2") (pintype "passive"))
      (node (ref "U2") (pin "1") (pinfunction "A_1") (pintype "passive"))
      (node (ref "U2") (pin "2") (pinfunction "EN_2") (pintype "passive"))
      (node (ref "U2") (pin "6") (pinfunction "SW_6") (pintype "passive"))
    )
    (net (code "25") (name "Net-(C3-PLUS)") (class "Default")
      (node (ref "C3") (pin "1") (pinfunction "PLUS_1") (pintype "passive"))
      (node (ref "C4") (pin "2") (pinfunction "2_2") (pintype "passive"))
      (node (ref "L1") (pin "2") (pinfunction "B_2") (pintype "passive"))
      (node (ref "L2") (pin "2") (pinfunction "2_2") (pintype "passive"))
      (node (ref "R2") (pin "2") (pinfunction "2_2") (pintype "passive"))
    )
    (net (code "26") (name "Net-(D1-A)") (class "Default")
      (node (ref "D1") (pin "2") (pinfunction "A_2") (pintype "passive"))
      (node (ref "IN") (pin "1") (pinfunction "2_1") (pintype "passive"))
      (node (ref "T1") (pin "PSG") (pinfunction "S1_PSG") (pintype "passive"))
    )
    (net (code "27") (name "Net-(D1-K)") (class "Default")
      (node (ref "D1") (pin "1") (pinfunction "K_1") (pintype "passive"))
      (node (ref "F1") (pin "2") (pinfunction "2_2") (pintype "passive"))
      (node (ref "T1") (pin "P") (pinfunction "P1_P") (pintype "passive"))
    )
    (net (code "28") (name "Net-(D2-A)") (class "Default")
      (node (ref "D2") (pin "2") (pinfunction "A_2") (pintype "passive"))
      (node (ref "Q1") (pin "1") (pinfunction "G_1") (pintype "passive"))
      (node (ref "Q2") (pin "3") (pinfunction "D_3") (pintype "passive"))
      (node (ref "R3") (pin "1") (pinfunction "1_1") (pintype "passive"))
    )
    (net (code "29") (name "Net-(D2-K)") (class "Default")
      (node (ref "D2") (pin "1") (pinfunction "K_1") (pintype "passive"))
      (node (ref "D3") (pin "1") (pinfunction "K_1") (pintype "passive"))
      (node (ref "R4") (pin "1") (pinfunction "1_1") (pintype "passive"))
      (node (ref "S1") (pin "1") (pinfunction "A_1") (pintype "passive"))
      (node (ref "S1") (pin "2") (pinfunction "A_2") (pintype "passive"))
    )
    (net (code "30") (name "Net-(ENCODER_MAIN1-5V)") (class "Default")
      (node (ref "C1008") (pin "2") (pinfunction "2_2") (pintype "passive"))
      (node (ref "ENCODER_MAIN1") (pin "2") (pinfunction "5V_2") (pintype "passive"))
      (node (ref "R1009") (pin "1") (pinfunction "1_1") (pintype "passive"))
      (node (ref "R1010") (pin "1") (pinfunction "1_1") (pintype "passive"))
    )
    (net (code "31") (name "Net-(ESP-1-URXD)") (class "Default")
      (node (ref "ESP-1") (pin "4") (pinfunction "URXD_4") (pintype "passive"))
      (node (ref "J1") (pin "31") (pinfunction "WRX_31") (pintype "passive"))
      (node (ref "M1") (pin "15") (pinfunction "RX_15") (pintype "passive"))
    )
    (net (code "32") (name "Net-(ESP-1-UTXD)") (class "Default")
      (node (ref "ESP-1") (pin "5") (pinfunction "UTXD_5") (pintype "passive"))
      (node (ref "J1") (pin "32") (pinfunction "WTX_32") (pintype "passive"))
      (node (ref "M1") (pin "16") (pinfunction "TX_16") (pintype "passive"))
    )
    (net (code "33") (name "Net-(IN-1)") (class "Default")
      (node (ref "F1") (pin "1") (pinfunction "1_1") (pintype "passive"))
      (node (ref "IN") (pin "2") (pinfunction "1_2") (pintype "passive"))
    )
    (net (code "34") (name "Net-(J1-CS)") (class "Default")
      (node (ref "J1") (pin "1") (pinfunction "CS_1") (pintype "passive"))
      (node (ref "U1") (pin "19") (pinfunction "CS_19") (pintype "passive"))
    )
    (net (code "35") (name "Net-(J1-DB0)") (class "Default")
      (node (ref "J1") (pin "6") (pinfunction "DB0_6") (pintype "passive"))
      (node (ref "U1") (pin "3") (pinfunction "D0_3") (pintype "passive"))
    )
    (net (code "36") (name "Net-(J1-DB1)") (class "Default")
      (node (ref "J1") (pin "7") (pinfunction "DB1_7") (pintype "passive"))
      (node (ref "U1") (pin "4") (pinfunction "D1_4") (pintype "passive"))
    )
    (net (code "37") (name "Net-(J1-DB2)") (class "Default")
      (node (ref "J1") (pin "8") (pinfunction "DB2_8") (pintype "passive"))
      (node (ref "U1") (pin "5") (pinfunction "D2_5") (pintype "passive"))
    )
    (net (code "38") (name "Net-(J1-DB3)") (class "Default")
      (node (ref "J1") (pin "9") (pinfunction "DB3_9") (pintype "passive"))
      (node (ref "U1") (pin "6") (pinfunction "D3_6") (pintype "passive"))
    )
    (net (code "39") (name "Net-(J1-DB4)") (class "Default")
      (node (ref "J1") (pin "10") (pinfunction "DB4_10") (pintype "passive"))
      (node (ref "U1") (pin "7") (pinfunction "D4_7") (pintype "passive"))
    )
    (net (code "40") (name "Net-(J1-DB5)") (class "Default")
      (node (ref "J1") (pin "11") (pinfunction "DB5_11") (pintype "passive"))
      (node (ref "U1") (pin "8") (pinfunction "D5_8") (pintype "passive"))
    )
    (net (code "41") (name "Net-(J1-DB6)") (class "Default")
      (node (ref "J1") (pin "12") (pinfunction "DB6_12") (pintype "passive"))
      (node (ref "U1") (pin "9") (pinfunction "D6_9") (pintype "passive"))
    )
    (net (code "42") (name "Net-(J1-DB7)") (class "Default")
      (node (ref "J1") (pin "13") (pinfunction "DB7_13") (pintype "passive"))
      (node (ref "U1") (pin "10") (pinfunction "D7_10") (pintype "passive"))
    )
    (net (code "43") (name "Net-(J1-DB8)") (class "Default")
      (node (ref "J1") (pin "14") (pinfunction "DB8_14") (pintype "passive"))
      (node (ref "U1") (pin "11") (pinfunction "D8_11") (pintype "passive"))
    )
    (net (code "44") (name "Net-(J1-DB9)") (class "Default")
      (node (ref "J1") (pin "15") (pinfunction "DB9_15") (pintype "passive"))
      (node (ref "U1") (pin "12") (pinfunction "D9_12") (pintype "passive"))
    )
    (net (code "45") (name "Net-(J1-DB10)") (class "Default")
      (node (ref "J1") (pin "16") (pinfunction "DB10_16") (pintype "passive"))
      (node (ref "U1") (pin "13") (pinfunction "D10_13") (pintype "passive"))
    )
    (net (code "46") (name "Net-(J1-DB11)") (class "Default")
      (node (ref "J1") (pin "17") (pinfunction "DB11_17") (pintype "passive"))
      (node (ref "U1") (pin "14") (pinfunction "D11_14") (pintype "passive"))
    )
    (net (code "47") (name "Net-(J1-DB12)") (class "Default")
      (node (ref "J1") (pin "18") (pinfunction "DB12_18") (pintype "passive"))
      (node (ref "U1") (pin "15") (pinfunction "D12_15") (pintype "passive"))
    )
    (net (code "48") (name "Net-(J1-DB13)") (class "Default")
      (node (ref "J1") (pin "19") (pinfunction "DB13_19") (pintype "passive"))
      (node (ref "U1") (pin "16") (pinfunction "D13_16") (pintype "passive"))
    )
    (net (code "49") (name "Net-(J1-DB14)") (class "Default")
      (node (ref "J1") (pin "20") (pinfunction "DB14_20") (pintype "passive"))
      (node (ref "U1") (pin "17") (pinfunction "D14_17") (pintype "passive"))
    )
    (net (code "50") (name "Net-(J1-DB15)") (class "Default")
      (node (ref "J1") (pin "21") (pinfunction "DB15_21") (pintype "passive"))
      (node (ref "U1") (pin "18") (pinfunction "D15_18") (pintype "passive"))
    )
    (net (code "51") (name "Net-(J1-RD)") (class "Default")
      (node (ref "J1") (pin "4") (pinfunction "RD_4") (pintype "passive"))
      (node (ref "U1") (pin "22") (pinfunction "RD_22") (pintype "passive"))
    )
    (net (code "52") (name "Net-(J1-RS)") (class "Default")
      (node (ref "J1") (pin "2") (pinfunction "RS_2") (pintype "passive"))
      (node (ref "U1") (pin "20") (pinfunction "RS_20") (pintype "passive"))
    )
    (net (code "53") (name "Net-(J1-RST)") (class "Default")
      (node (ref "J1") (pin "5") (pinfunction "RST_5") (pintype "passive"))
      (node (ref "U1") (pin "23") (pinfunction "RST_23") (pintype "passive"))
    )
    (net (code "54") (name "Net-(J1-WR)") (class "Default")
      (node (ref "J1") (pin "3") (pinfunction "WR_3") (pintype "passive"))
      (node (ref "U1") (pin "21") (pinfunction "WR_21") (pintype "passive"))
    )
    (net (code "55") (name "Net-(J3-Pad1)") (class "Default")
      (node (ref "J3") (pin "1") (pinfunction "1_1") (pintype "passive"))
      (node (ref "R26") (pin "1") (pinfunction "1_1") (pintype "passive"))
      (node (ref "U5") (pin "1") (pinfunction "1_1") (pintype "passive"))
    )
    (net (code "56") (name "Net-(J3-Pad2)") (class "Default")
      (node (ref "J3") (pin "2") (pinfunction "2_2") (pintype "passive"))
      (node (ref "R25") (pin "1") (pinfunction "1_1") (pintype "passive"))
      (node (ref "U4") (pin "1") (pinfunction "1_1") (pintype "passive"))
    )
    (net (code "57") (name "Net-(J3-Pad6)") (class "Default")
      (node (ref "J3") (pin "6") (pinfunction "6_6") (pintype "passive"))
      (node (ref "R16") (pin "1") (pinfunction "1_1") (pintype "passive"))
    )
    (net (code "58") (name "Net-(L2-Pad1)") (class "Default")
      (node (ref "L2") (pin "1") (pinfunction "1_1") (pintype "passive"))
      (node (ref "U2") (pin "7") (pinfunction "SW_7") (pintype "passive"))
    )
    (net (code "59") (name "Net-(M1-GPIO0)") (class "Default")
      (node (ref "M1") (pin "12") (pinfunction "GPIO0_12") (pintype "passive"))
      (node (ref "R1005") (pin "2") (pinfunction "2_2") (pintype "passive"))
      (node (ref "R1006") (pin "1") (pinfunction "1_1") (pintype "passive"))
    )
    (net (code "60") (name "Net-(M1-GPIO2)") (class "Default")
      (node (ref "M1") (pin "11") (pinfunction "GPIO2_11") (pintype "passive"))
      (node (ref "R1003") (pin "2") (pinfunction "2_2") (pintype "passive"))
      (node (ref "R1004") (pin "1") (pinfunction "1_1") (pintype "passive"))
    )
    (net (code "61") (name "Net-(M1-GPIO15)") (class "Default")
      (node (ref "M1") (pin "10") (pinfunction "GPIO15_10") (pintype "passive"))
      (node (ref "R1001") (pin "2") (pinfunction "2_2") (pintype "passive"))
      (node (ref "R1002") (pin "1") (pinfunction "1_1") (pintype "passive"))
    )
    (net (code "62") (name "Net-(MIC_OUT-GND)") (class "Default")
      (node (ref "C12") (pin "2") (pinfunction "2_2") (pintype "power_in"))
      (node (ref "MIC_OUT") (pin "3") (pinfunction "GND_3") (pintype "passive"))
      (node (ref "R16") (pin "2") (pinfunction "2_2") (pintype "passive"))
    )
    (net (code "63") (name "Net-(MIC_OUT-TX)") (class "Default")
      (node (ref "J3") (pin "5") (pinfunction "5_5") (pintype "passive"))
      (node (ref "MIC_OUT") (pin "2") (pinfunction "TX_2") (pintype "passive"))
    )
    (net (code "64") (name "Net-(MOTHERBOARD-1)") (class "Default")
      (node (ref "F2") (pin "2") (pinfunction "2_2") (pintype "passive"))
      (node (ref "MOTHERBOARD") (pin "2") (pinfunction "1_2") (pintype "passive"))
    )
    (net (code "65") (name "Net-(R6-W)") (class "Default")
      (node (ref "R1007") (pin "1") (pinfunction "1_1") (pintype "passive"))
      (node (ref "R6") (pin "2") (pinfunction "W_2") (pintype "passive"))
    )
    (net (code "66") (name "Net-(R7-W)") (class "Default")
      (node (ref "R1008") (pin "1") (pinfunction "1_1") (pintype "passive"))
      (node (ref "R7") (pin "2") (pinfunction "W_2") (pintype "passive"))
    )
    (net (code "67") (name "Net-(R12-Pad1)") (class "Default")
      (node (ref "R12") (pin "1") (pinfunction "1_1") (pintype "passive"))
      (node (ref "R17") (pin "2") (pinfunction "2_2") (pintype "passive"))
      (node (ref "S3") (pin "1") (pinfunction "A_1") (pintype "passive"))
    )
    (net (code "68") (name "Net-(R13-Pad1)") (class "Default")
      (node (ref "R13") (pin "1") (pinfunction "1_1") (pintype "passive"))
      (node (ref "R18") (pin "2") (pinfunction "2_2") (pintype "passive"))
      (node (ref "S2") (pin "1") (pinfunction "A_1") (pintype "passive"))
    )
    (net (code "69") (name "Net-(R14-Pad1)") (class "Default")
      (node (ref "R14") (pin "1") (pinfunction "1_1") (pintype "passive"))
      (node (ref "R19") (pin "2") (pinfunction "2_2") (pintype "passive"))
      (node (ref "S4") (pin "1") (pinfunction "A_1") (pintype "passive"))
      (node (ref "S4") (pin "2") (pinfunction "A_2") (pintype "passive"))
    )
    (net (code "70") (name "Net-(R15-Pad1)") (class "Default")
      (node (ref "R15") (pin "1") (pinfunction "1_1") (pintype "passive"))
      (node (ref "R20") (pin "2") (pinfunction "2_2") (pintype "passive"))
      (node (ref "S5") (pin "1") (pinfunction "A_1") (pintype "passive"))
    )
    (net (code "71") (name "Net-(R17-Pad1)") (class "Default")
      (node (ref "R17") (pin "1") (pinfunction "1_1") (pintype "passive"))
      (node (ref "R21") (pin "2") (pinfunction "2_2") (pintype "passive"))
      (node (ref "S7") (pin "1") (pinfunction "A_1") (pintype "passive"))
    )
    (net (code "72") (name "Net-(R18-Pad1)") (class "Default")
      (node (ref "R18") (pin "1") (pinfunction "1_1") (pintype "passive"))
      (node (ref "R22") (pin "2") (pinfunction "2_2") (pintype "passive"))
      (node (ref "S6") (pin "1") (pinfunction "A_1") (pintype "passive"))
    )
    (net (code "73") (name "Net-(R19-Pad1)") (class "Default")
      (node (ref "R19") (pin "1") (pinfunction "1_1") (pintype "passive"))
      (node (ref "R23") (pin "2") (pinfunction "2_2") (pintype "passive"))
      (node (ref "S8") (pin "1") (pinfunction "A_1") (pintype "passive"))
      (node (ref "S8") (pin "2") (pinfunction "A_2") (pintype "passive"))
    )
    (net (code "74") (name "Net-(R20-Pad1)") (class "Default")
      (node (ref "R20") (pin "1") (pinfunction "1_1") (pintype "passive"))
      (node (ref "R24") (pin "2") (pinfunction "2_2") (pintype "passive"))
      (node (ref "S9") (pin "1") (pinfunction "A_1") (pintype "passive"))
    )
    (net (code "75") (name "Net-(R21-Pad1)") (class "Default")
      (node (ref "R21") (pin "1") (pinfunction "1_1") (pintype "passive"))
      (node (ref "S11") (pin "1") (pinfunction "A_1") (pintype "passive"))
    )
    (net (code "76") (name "Net-(R22-Pad1)") (class "Default")
      (node (ref "R22") (pin "1") (pinfunction "1_1") (pintype "passive"))
      (node (ref "S10") (pin "1") (pinfunction "A_1") (pintype "passive"))
    )
    (net (code "77") (name "Net-(R23-Pad1)") (class "Default")
      (node (ref "R23") (pin "1") (pinfunction "1_1") (pintype "passive"))
      (node (ref "S12") (pin "1") (pinfunction "A_1") (pintype "passive"))
      (node (ref "S12") (pin "2") (pinfunction "A_2") (pintype "passive"))
    )
    (net (code "78") (name "Net-(U2-SYN)") (class "Default")
      (node (ref "R1011") (pin "1") (pinfunction "1_1") (pintype "passive"))
      (node (ref "U2") (pin "5") (pinfunction "SYN_5") (pintype "passive"))
    )
    (net (code "79") (name "Net-(U2-VFB)") (class "Default")
      (node (ref "R1") (pin "2") (pinfunction "2_2") (pintype "passive"))
      (node (ref "R2") (pin "1") (pinfunction "1_1") (pintype "passive"))
      (node (ref "U2") (pin "3") (pinfunction "VFB_3") (pintype "passive"))
    )
    (net (code "80") (name "Net-(U3-CH0)") (class "Default")
      (node (ref "C1002") (pin "2") (pinfunction "2_2") (pintype "passive"))
      (node (ref "R1007") (pin "2") (pinfunction "2_2") (pintype "passive"))
      (node (ref "U3") (pin "1") (pinfunction "CH0_1") (pintype "passive"))
    )
    (net (code "81") (name "Net-(U3-CH1)") (class "Default")
      (node (ref "C1003") (pin "2") (pinfunction "2_2") (pintype "passive"))
      (node (ref "R1008") (pin "2") (pinfunction "2_2") (pintype "passive"))
      (node (ref "U3") (pin "2") (pinfunction "CH1_2") (pintype "passive"))
    )
    (net (code "82") (name "Net-(U3-CH4)") (class "Default")
      (node (ref "R15") (pin "2") (pinfunction "2_2") (pintype "passive"))
      (node (ref "R9") (pin "1") (pinfunction "1_1") (pintype "passive"))
      (node (ref "U3") (pin "5") (pinfunction "CH4_5") (pintype "passive"))
    )
    (net (code "83") (name "Net-(U3-CH5)") (class "Default")
      (node (ref "R11") (pin "1") (pinfunction "1_1") (pintype "passive"))
      (node (ref "R14") (pin "2") (pinfunction "2_2") (pintype "passive"))
      (node (ref "U3") (pin "6") (pinfunction "CH5_6") (pintype "passive"))
    )
    (net (code "84") (name "Net-(U3-CH6)") (class "Default")
      (node (ref "R10") (pin "1") (pinfunction "1_1") (pintype "passive"))
      (node (ref "R12") (pin "2") (pinfunction "2_2") (pintype "passive"))
      (node (ref "U3") (pin "7") (pinfunction "CH6_7") (pintype "passive"))
    )
    (net (code "85") (name "Net-(U3-CH7)") (class "Default")
      (node (ref "R13") (pin "2") (pinfunction "2_2") (pintype "passive"))
      (node (ref "R8") (pin "1") (pinfunction "1_1") (pintype "passive"))
      (node (ref "U3") (pin "8") (pinfunction "CH7_8") (pintype "passive"))
    )
    (net (code "86") (name "VCC12_IN") (class "Default")
      (node (ref "Q1") (pin "3") (pinfunction "S_3") (pintype "passive"))
      (node (ref "R3") (pin "2") (pinfunction "2_2") (pintype "passive"))
      (node (ref "R4") (pin "2") (pinfunction "2_2") (pintype "passive"))
      (node (ref "T1") (pin "LCP") (pinfunction "P2_LCP") (pintype "passive"))
    )
    (net (code "87") (name "unconnected-(ESP-1-GPIO0-Pad3)") (class "Default")
      (node (ref "ESP-1") (pin "3") (pinfunction "GPIO0_3") (pintype "passive"))
    )
    (net (code "88") (name "unconnected-(ESP-1-GPIO2-Pad2)") (class "Default")
      (node (ref "ESP-1") (pin "2") (pinfunction "GPIO2_2") (pintype "passive"))
    )
    (net (code "89") (name "unconnected-(ESP-1-GPIO16-Pad7)") (class "Default")
      (node (ref "ESP-1") (pin "7") (pinfunction "GPIO16_7") (pintype "passive"))
    )
    (net (code "90") (name "unconnected-(J2-DAT1-Pad8)") (class "Default")
      (node (ref "J2") (pin "8") (pinfunction "DAT1_8") (pintype "passive"))
    )
    (net (code "91") (name "unconnected-(J2-DAT2-Pad1)") (class "Default")
      (node (ref "J2") (pin "1") (pinfunction "DAT2_1") (pintype "passive"))
    )
    (net (code "92") (name "unconnected-(J3-Pad0)") (class "Default")
      (node (ref "J3") (pin "0") (pinfunction "0_0") (pintype "passive"))
    )
    (net (code "93") (name "unconnected-(M1-ADC-Pad2)") (class "Default")
      (node (ref "M1") (pin "2") (pinfunction "ADC_2") (pintype "passive"))
    )
    (net (code "94") (name "unconnected-(M1-GPIO4-Pad13)") (class "Default")
      (node (ref "M1") (pin "13") (pinfunction "GPIO4_13") (pintype "passive"))
    )
    (net (code "95") (name "unconnected-(M1-GPIO5-Pad14)") (class "Default")
      (node (ref "M1") (pin "14") (pinfunction "GPIO5_14") (pintype "passive"))
    )
    (net (code "96") (name "unconnected-(M1-GPIO12-Pad6)") (class "Default")
      (node (ref "M1") (pin "6") (pinfunction "GPIO12_6") (pintype "passive"))
    )
    (net (code "97") (name "unconnected-(M1-GPIO13-Pad7)") (class "Default")
      (node (ref "M1") (pin "7") (pinfunction "GPIO13_7") (pintype "passive"))
    )
    (net (code "98") (name "unconnected-(M1-GPIO14-Pad5)") (class "Default")
      (node (ref "M1") (pin "5") (pinfunction "GPIO14_5") (pintype "passive"))
    )
    (net (code "99") (name "unconnected-(M1-GPIO16-Pad4)") (class "Default")
      (node (ref "M1") (pin "4") (pinfunction "GPIO16_4") (pintype "passive"))
    )
    (net (code "100") (name "unconnected-(M1-RST-Pad1)") (class "Default")
      (node (ref "M1") (pin "1") (pinfunction "RST_1") (pintype "passive"))
    )
    (net (code "101") (name "unconnected-(U1-INT-Pad28)") (class "Default")
      (node (ref "U1") (pin "28") (pinfunction "INT_28") (pintype "passive"))
    )
    (net (code "102") (name "unconnected-(U1-NC-Pad1)") (class "Default")
      (node (ref "U1") (pin "1") (pinfunction "NC_1") (pintype "passive"))
    )
    (net (code "103") (name "unconnected-(U1-NC-Pad24)") (class "Default")
      (node (ref "U1") (pin "24") (pinfunction "NC_24") (pintype "passive"))
    )
    (net (code "104") (name "unconnected-(U1-NC-Pad27)") (class "Default")
      (node (ref "U1") (pin "27") (pinfunction "NC_27") (pintype "passive"))
    )
    (net (code "105") (name "unconnected-(U1-WAIT-Pad29)") (class "Default")
      (node (ref "U1") (pin "29") (pinfunction "WAIT_29") (pintype "passive"))
    )
  )
)
